# MicroBit_Robot_Interface_RevA.net
KiCad netlist of a schematic drawn in EAGLE
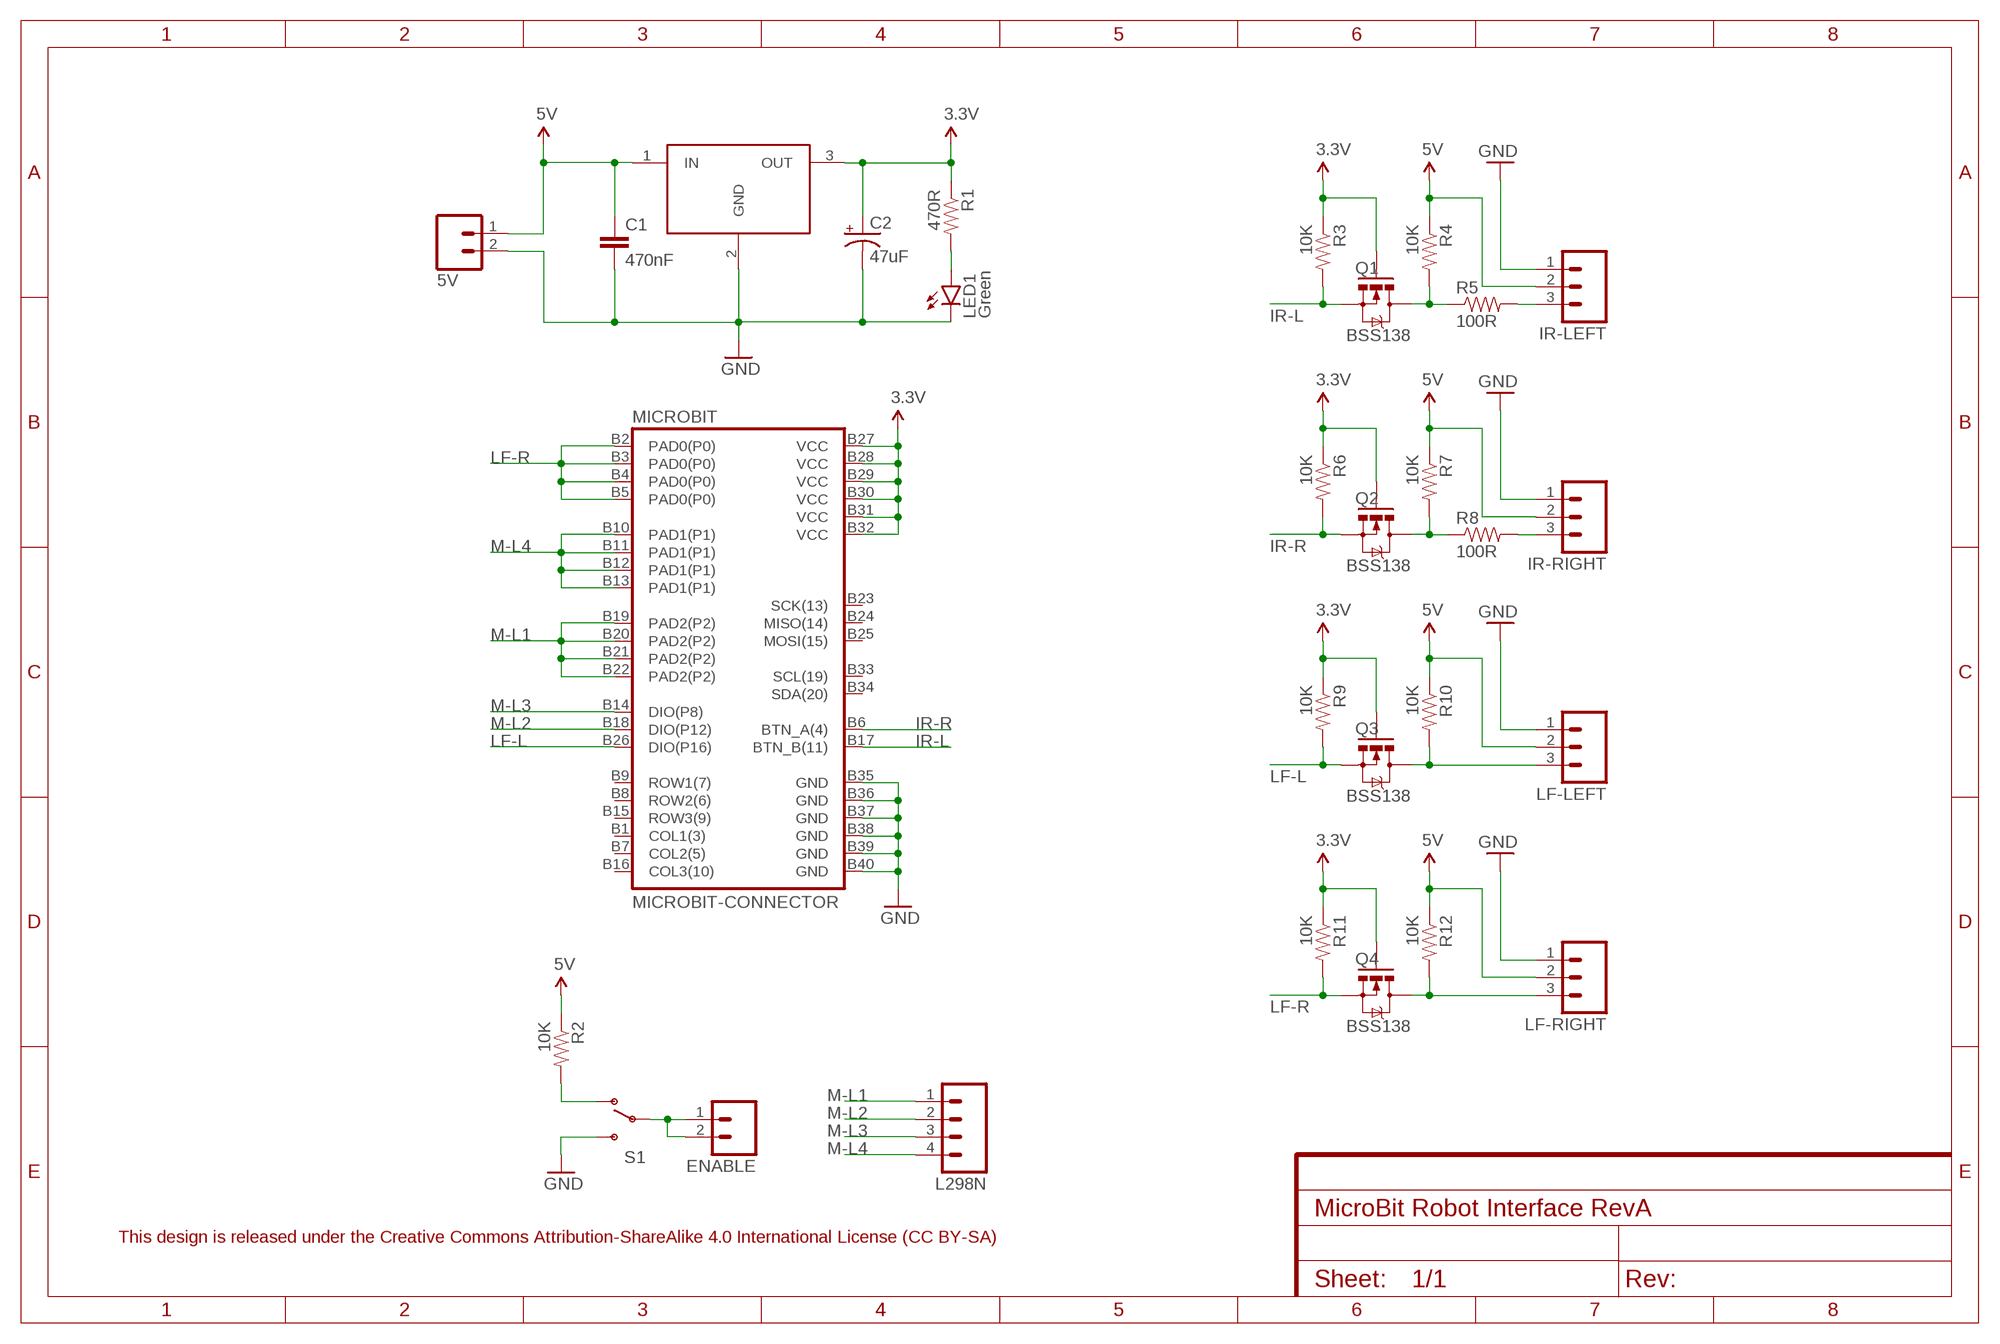
[diagram p0: schematic, sheet 1]

(export (version "E")
  (design (tool "Eeschema 10.0.6"))
  (components
    (comp (ref "5V")
      (value "MCOMP_SCREWTERM_2PIN5MM")
      (footprint "eagle-import:MCOMP-SCREWTERMINAL-5MM-2")
      (libsource (lib "eagle-import") (part "MCOMP_SCREWTERM_2PIN5MM"))
    )
    (comp (ref "C1")
      (value "470nF")
      (footprint "eagle-import:0603-CAP")
      (libsource (lib "eagle-import") (part "CAP0603-CAP"))
    )
    (comp (ref "C2")
      (value "47uF")
      (footprint "eagle-import:CPOL-RADIAL-100UF-25V")
      (libsource (lib "eagle-import") (part "CAP_POLPTH1"))
    )
    (comp (ref "ENABLE")
      (value "M02PTH")
      (footprint "eagle-import:1X02")
      (libsource (lib "eagle-import") (part "M02PTH"))
    )
    (comp (ref "IR-LEFT")
      (value "M03PTH")
      (footprint "eagle-import:1X03")
      (libsource (lib "eagle-import") (part "M03PTH"))
    )
    (comp (ref "IR-RIGHT")
      (value "M03PTH")
      (footprint "eagle-import:1X03")
      (libsource (lib "eagle-import") (part "M03PTH"))
    )
    (comp (ref "L298N")
      (value "M04PTH")
      (footprint "eagle-import:1X04")
      (libsource (lib "eagle-import") (part "M04PTH"))
    )
    (comp (ref "LED1")
      (value "Green")
      (footprint "eagle-import:LED3MM")
      (libsource (lib "eagle-import") (part "LED3MM"))
    )
    (comp (ref "LF-LEFT")
      (value "M03PTH")
      (footprint "eagle-import:1X03")
      (libsource (lib "eagle-import") (part "M03PTH"))
    )
    (comp (ref "LF-RIGHT")
      (value "M03PTH")
      (footprint "eagle-import:1X03")
      (libsource (lib "eagle-import") (part "M03PTH"))
    )
    (comp (ref "MICROBIT")
      (value "MICROBIT-CONNECTOR")
      (footprint "eagle-import:RBB40DHHN_MICROBIT")
      (libsource (lib "eagle-import") (part "MICROBIT-CONNECTOR"))
    )
    (comp (ref "Q1")
      (value "BSS138")
      (footprint "eagle-import:SOT23-3")
      (libsource (lib "eagle-import") (part "MOSFET-NCHANNELBSS138"))
    )
    (comp (ref "Q2")
      (value "BSS138")
      (footprint "eagle-import:SOT23-3")
      (libsource (lib "eagle-import") (part "MOSFET-NCHANNELBSS138"))
    )
    (comp (ref "Q3")
      (value "BSS138")
      (footprint "eagle-import:SOT23-3")
      (libsource (lib "eagle-import") (part "MOSFET-NCHANNELBSS138"))
    )
    (comp (ref "Q4")
      (value "BSS138")
      (footprint "eagle-import:SOT23-3")
      (libsource (lib "eagle-import") (part "MOSFET-NCHANNELBSS138"))
    )
    (comp (ref "R1")
      (value "470R")
      (footprint "eagle-import:0603-RES")
      (libsource (lib "eagle-import") (part "RESISTOR0603-RES"))
    )
    (comp (ref "R2")
      (value "10K")
      (footprint "eagle-import:0603-RES")
      (libsource (lib "eagle-import") (part "RESISTOR0603-RES"))
    )
    (comp (ref "R3")
      (value "10K")
      (footprint "eagle-import:0603-RES")
      (libsource (lib "eagle-import") (part "RESISTOR0603-RES"))
    )
    (comp (ref "R4")
      (value "10K")
      (footprint "eagle-import:0603-RES")
      (libsource (lib "eagle-import") (part "RESISTOR0603-RES"))
    )
    (comp (ref "R5")
      (value "100R")
      (footprint "eagle-import:0603-RES")
      (libsource (lib "eagle-import") (part "RESISTOR0603-RES"))
    )
    (comp (ref "R6")
      (value "10K")
      (footprint "eagle-import:0603-RES")
      (libsource (lib "eagle-import") (part "RESISTOR0603-RES"))
    )
    (comp (ref "R7")
      (value "10K")
      (footprint "eagle-import:0603-RES")
      (libsource (lib "eagle-import") (part "RESISTOR0603-RES"))
    )
    (comp (ref "R8")
      (value "100R")
      (footprint "eagle-import:0603-RES")
      (libsource (lib "eagle-import") (part "RESISTOR0603-RES"))
    )
    (comp (ref "R9")
      (value "10K")
      (footprint "eagle-import:0603-RES")
      (libsource (lib "eagle-import") (part "RESISTOR0603-RES"))
    )
    (comp (ref "R10")
      (value "10K")
      (footprint "eagle-import:0603-RES")
      (libsource (lib "eagle-import") (part "RESISTOR0603-RES"))
    )
    (comp (ref "R11")
      (value "10K")
      (footprint "eagle-import:0603-RES")
      (libsource (lib "eagle-import") (part "RESISTOR0603-RES"))
    )
    (comp (ref "R12")
      (value "10K")
      (footprint "eagle-import:0603-RES")
      (libsource (lib "eagle-import") (part "RESISTOR0603-RES"))
    )
    (comp (ref "S1")
      (value "KNITTER-SWITCH-MFP106D")
      (footprint "eagle-import:KNITTER-SWITCH-MFP106D")
      (libsource (lib "eagle-import") (part "KNITTER-SWITCH-MFP106D"))
    )
    (comp (ref "VR1")
      (value "LM3940IMP-3.3")
      (footprint "eagle-import:SOT223")
      (libsource (lib "eagle-import") (part "LM3940IMP-3.3"))
    )
  )
  (nets
    (net (code "1") (name "/IR-L") (class "Default")
      (node (ref "MICROBIT") (pin "B17") (pinfunction "BTN_B(11)_B17") (pintype "input"))
      (node (ref "Q1") (pin "2") (pinfunction "S_2") (pintype "passive"))
      (node (ref "R3") (pin "2") (pinfunction "2_2") (pintype "passive"))
    )
    (net (code "2") (name "/IR-R") (class "Default")
      (node (ref "MICROBIT") (pin "B6") (pinfunction "BTN_A(4)_B6") (pintype "input"))
      (node (ref "Q2") (pin "2") (pinfunction "S_2") (pintype "passive"))
      (node (ref "R6") (pin "2") (pinfunction "2_2") (pintype "passive"))
    )
    (net (code "3") (name "/LF-L") (class "Default")
      (node (ref "MICROBIT") (pin "B26") (pinfunction "DIO(P16)_B26") (pintype "bidirectional"))
      (node (ref "Q3") (pin "2") (pinfunction "S_2") (pintype "passive"))
      (node (ref "R9") (pin "2") (pinfunction "2_2") (pintype "passive"))
    )
    (net (code "4") (name "/LF-R") (class "Default")
      (node (ref "MICROBIT") (pin "B2") (pinfunction "PAD0(P0)_B2") (pintype "bidirectional"))
      (node (ref "MICROBIT") (pin "B3") (pinfunction "PAD0(P0)_B3") (pintype "bidirectional"))
      (node (ref "MICROBIT") (pin "B4") (pinfunction "PAD0(P0)_B4") (pintype "bidirectional"))
      (node (ref "MICROBIT") (pin "B5") (pinfunction "PAD0(P0)_B5") (pintype "bidirectional"))
      (node (ref "Q4") (pin "2") (pinfunction "S_2") (pintype "passive"))
      (node (ref "R11") (pin "2") (pinfunction "2_2") (pintype "passive"))
    )
    (net (code "5") (name "/M-L1") (class "Default")
      (node (ref "L298N") (pin "1") (pinfunction "1_1") (pintype "passive"))
      (node (ref "MICROBIT") (pin "B19") (pinfunction "PAD2(P2)_B19") (pintype "bidirectional"))
      (node (ref "MICROBIT") (pin "B20") (pinfunction "PAD2(P2)_B20") (pintype "bidirectional"))
      (node (ref "MICROBIT") (pin "B21") (pinfunction "PAD2(P2)_B21") (pintype "bidirectional"))
      (node (ref "MICROBIT") (pin "B22") (pinfunction "PAD2(P2)_B22") (pintype "bidirectional"))
    )
    (net (code "6") (name "/M-L2") (class "Default")
      (node (ref "L298N") (pin "2") (pinfunction "2_2") (pintype "passive"))
      (node (ref "MICROBIT") (pin "B18") (pinfunction "DIO(P12)_B18") (pintype "bidirectional"))
    )
    (net (code "7") (name "/M-L3") (class "Default")
      (node (ref "L298N") (pin "3") (pinfunction "3_3") (pintype "passive"))
      (node (ref "MICROBIT") (pin "B14") (pinfunction "DIO(P8)_B14") (pintype "bidirectional"))
    )
    (net (code "8") (name "/M-L4") (class "Default")
      (node (ref "L298N") (pin "4") (pinfunction "4_4") (pintype "passive"))
      (node (ref "MICROBIT") (pin "B10") (pinfunction "PAD1(P1)_B10") (pintype "bidirectional"))
      (node (ref "MICROBIT") (pin "B11") (pinfunction "PAD1(P1)_B11") (pintype "bidirectional"))
      (node (ref "MICROBIT") (pin "B12") (pinfunction "PAD1(P1)_B12") (pintype "bidirectional"))
      (node (ref "MICROBIT") (pin "B13") (pinfunction "PAD1(P1)_B13") (pintype "bidirectional"))
    )
    (net (code "9") (name "3.3V") (class "Default")
      (node (ref "C2") (pin "1") (pinfunction "+_1") (pintype "passive"))
      (node (ref "MICROBIT") (pin "B27") (pinfunction "VCC_B27") (pintype "power_in"))
      (node (ref "MICROBIT") (pin "B28") (pinfunction "VCC_B28") (pintype "power_in"))
      (node (ref "MICROBIT") (pin "B29") (pinfunction "VCC_B29") (pintype "power_in"))
      (node (ref "MICROBIT") (pin "B30") (pinfunction "VCC_B30") (pintype "power_in"))
      (node (ref "MICROBIT") (pin "B31") (pinfunction "VCC_B31") (pintype "power_in"))
      (node (ref "MICROBIT") (pin "B32") (pinfunction "VCC_B32") (pintype "power_in"))
      (node (ref "Q1") (pin "1") (pinfunction "G_1") (pintype "passive"))
      (node (ref "Q2") (pin "1") (pinfunction "G_1") (pintype "passive"))
      (node (ref "Q3") (pin "1") (pinfunction "G_1") (pintype "passive"))
      (node (ref "Q4") (pin "1") (pinfunction "G_1") (pintype "passive"))
      (node (ref "R1") (pin "1") (pinfunction "1_1") (pintype "passive"))
      (node (ref "R11") (pin "1") (pinfunction "1_1") (pintype "passive"))
      (node (ref "R3") (pin "1") (pinfunction "1_1") (pintype "passive"))
      (node (ref "R6") (pin "1") (pinfunction "1_1") (pintype "passive"))
      (node (ref "R9") (pin "1") (pinfunction "1_1") (pintype "passive"))
      (node (ref "VR1") (pin "3") (pinfunction "OUT_3") (pintype "power_in"))
    )
    (net (code "10") (name "5V") (class "Default")
      (node (ref "5V") (pin "1") (pinfunction "1_1") (pintype "passive"))
      (node (ref "C1") (pin "1") (pinfunction "1_1") (pintype "passive"))
      (node (ref "IR-LEFT") (pin "2") (pinfunction "2_2") (pintype "passive"))
      (node (ref "IR-RIGHT") (pin "2") (pinfunction "2_2") (pintype "passive"))
      (node (ref "LF-LEFT") (pin "2") (pinfunction "2_2") (pintype "passive"))
      (node (ref "LF-RIGHT") (pin "2") (pinfunction "2_2") (pintype "passive"))
      (node (ref "R10") (pin "1") (pinfunction "1_1") (pintype "passive"))
      (node (ref "R12") (pin "1") (pinfunction "1_1") (pintype "passive"))
      (node (ref "R2") (pin "1") (pinfunction "1_1") (pintype "passive"))
      (node (ref "R4") (pin "1") (pinfunction "1_1") (pintype "passive"))
      (node (ref "R7") (pin "1") (pinfunction "1_1") (pintype "passive"))
      (node (ref "VR1") (pin "1") (pinfunction "IN_1") (pintype "power_in"))
    )
    (net (code "11") (name "GND") (class "Default")
      (node (ref "5V") (pin "2") (pinfunction "2_2") (pintype "passive"))
      (node (ref "C1") (pin "2") (pinfunction "2_2") (pintype "passive"))
      (node (ref "C2") (pin "2") (pinfunction "-_2") (pintype "passive"))
      (node (ref "IR-LEFT") (pin "1") (pinfunction "1_1") (pintype "passive"))
      (node (ref "IR-RIGHT") (pin "1") (pinfunction "1_1") (pintype "passive"))
      (node (ref "LED1") (pin "K") (pinfunction "C_K") (pintype "passive"))
      (node (ref "LF-LEFT") (pin "1") (pinfunction "1_1") (pintype "passive"))
      (node (ref "LF-RIGHT") (pin "1") (pinfunction "1_1") (pintype "passive"))
      (node (ref "MICROBIT") (pin "B35") (pinfunction "GND_B35") (pintype "power_in"))
      (node (ref "MICROBIT") (pin "B36") (pinfunction "GND_B36") (pintype "power_in"))
      (node (ref "MICROBIT") (pin "B37") (pinfunction "GND_B37") (pintype "power_in"))
      (node (ref "MICROBIT") (pin "B38") (pinfunction "GND_B38") (pintype "power_in"))
      (node (ref "MICROBIT") (pin "B39") (pinfunction "GND_B39") (pintype "power_in"))
      (node (ref "MICROBIT") (pin "B40") (pinfunction "GND_B40") (pintype "power_in"))
      (node (ref "S1") (pin "P$2") (pinfunction "POS2_P$2") (pintype "passive"))
      (node (ref "VR1") (pin "2") (pinfunction "GND_2") (pintype "power_in"))
    )
    (net (code "12") (name "Net-(IR-LEFT-Pad3)") (class "Default")
      (node (ref "IR-LEFT") (pin "3") (pinfunction "3_3") (pintype "passive"))
      (node (ref "R5") (pin "2") (pinfunction "2_2") (pintype "passive"))
    )
    (net (code "13") (name "Net-(IR-RIGHT-Pad3)") (class "Default")
      (node (ref "IR-RIGHT") (pin "3") (pinfunction "3_3") (pintype "passive"))
      (node (ref "R8") (pin "2") (pinfunction "2_2") (pintype "passive"))
    )
    (net (code "14") (name "Net-(LED1-PadA)") (class "Default")
      (node (ref "LED1") (pin "A") (pinfunction "A_A") (pintype "passive"))
      (node (ref "R1") (pin "2") (pinfunction "2_2") (pintype "passive"))
    )
    (net (code "15") (name "Net-(Q1-D)") (class "Default")
      (node (ref "Q1") (pin "3") (pinfunction "D_3") (pintype "passive"))
      (node (ref "R4") (pin "2") (pinfunction "2_2") (pintype "passive"))
      (node (ref "R5") (pin "1") (pinfunction "1_1") (pintype "passive"))
    )
    (net (code "16") (name "Net-(Q2-D)") (class "Default")
      (node (ref "Q2") (pin "3") (pinfunction "D_3") (pintype "passive"))
      (node (ref "R7") (pin "2") (pinfunction "2_2") (pintype "passive"))
      (node (ref "R8") (pin "1") (pinfunction "1_1") (pintype "passive"))
    )
    (net (code "17") (name "Net-(Q3-D)") (class "Default")
      (node (ref "LF-LEFT") (pin "3") (pinfunction "3_3") (pintype "passive"))
      (node (ref "Q3") (pin "3") (pinfunction "D_3") (pintype "passive"))
      (node (ref "R10") (pin "2") (pinfunction "2_2") (pintype "passive"))
    )
    (net (code "18") (name "Net-(Q4-D)") (class "Default")
      (node (ref "LF-RIGHT") (pin "3") (pinfunction "3_3") (pintype "passive"))
      (node (ref "Q4") (pin "3") (pinfunction "D_3") (pintype "passive"))
      (node (ref "R12") (pin "2") (pinfunction "2_2") (pintype "passive"))
    )
    (net (code "19") (name "Net-(S1-COMMON)") (class "Default")
      (node (ref "ENABLE") (pin "1") (pinfunction "1_1") (pintype "passive"))
      (node (ref "ENABLE") (pin "2") (pinfunction "2_2") (pintype "passive"))
      (node (ref "S1") (pin "WIPER") (pinfunction "COMMON_WIPER") (pintype "passive"))
    )
    (net (code "20") (name "Net-(S1-POS1)") (class "Default")
      (node (ref "R2") (pin "2") (pinfunction "2_2") (pintype "passive"))
      (node (ref "S1") (pin "P$1") (pinfunction "POS1_P$1") (pintype "passive"))
    )
    (net (code "21") (name "unconnected-(MICROBIT-COL1(3)-PadB1)") (class "Default")
      (node (ref "MICROBIT") (pin "B1") (pinfunction "COL1(3)_B1") (pintype "output"))
    )
    (net (code "22") (name "unconnected-(MICROBIT-COL2(5)-PadB7)") (class "Default")
      (node (ref "MICROBIT") (pin "B7") (pinfunction "COL2(5)_B7") (pintype "output"))
    )
    (net (code "23") (name "unconnected-(MICROBIT-COL3(10)-PadB16)") (class "Default")
      (node (ref "MICROBIT") (pin "B16") (pinfunction "COL3(10)_B16") (pintype "output"))
    )
    (net (code "24") (name "unconnected-(MICROBIT-MISO(14)-PadB24)") (class "Default")
      (node (ref "MICROBIT") (pin "B24") (pinfunction "MISO(14)_B24") (pintype "bidirectional"))
    )
    (net (code "25") (name "unconnected-(MICROBIT-MOSI(15)-PadB25)") (class "Default")
      (node (ref "MICROBIT") (pin "B25") (pinfunction "MOSI(15)_B25") (pintype "bidirectional"))
    )
    (net (code "26") (name "unconnected-(MICROBIT-ROW1(7)-PadB9)") (class "Default")
      (node (ref "MICROBIT") (pin "B9") (pinfunction "ROW1(7)_B9") (pintype "output"))
    )
    (net (code "27") (name "unconnected-(MICROBIT-ROW2(6)-PadB8)") (class "Default")
      (node (ref "MICROBIT") (pin "B8") (pinfunction "ROW2(6)_B8") (pintype "output"))
    )
    (net (code "28") (name "unconnected-(MICROBIT-ROW3(9)-PadB15)") (class "Default")
      (node (ref "MICROBIT") (pin "B15") (pinfunction "ROW3(9)_B15") (pintype "output"))
    )
    (net (code "29") (name "unconnected-(MICROBIT-SCK(13)-PadB23)") (class "Default")
      (node (ref "MICROBIT") (pin "B23") (pinfunction "SCK(13)_B23") (pintype "bidirectional"))
    )
    (net (code "30") (name "unconnected-(MICROBIT-SCL(19)-PadB33)") (class "Default")
      (node (ref "MICROBIT") (pin "B33") (pinfunction "SCL(19)_B33") (pintype "bidirectional"))
    )
    (net (code "31") (name "unconnected-(MICROBIT-SDA(20)-PadB34)") (class "Default")
      (node (ref "MICROBIT") (pin "B34") (pinfunction "SDA(20)_B34") (pintype "bidirectional"))
    )
  )
)
